# max10_schematic.net
KiCad netlist of a schematic drawn in Altium Designer
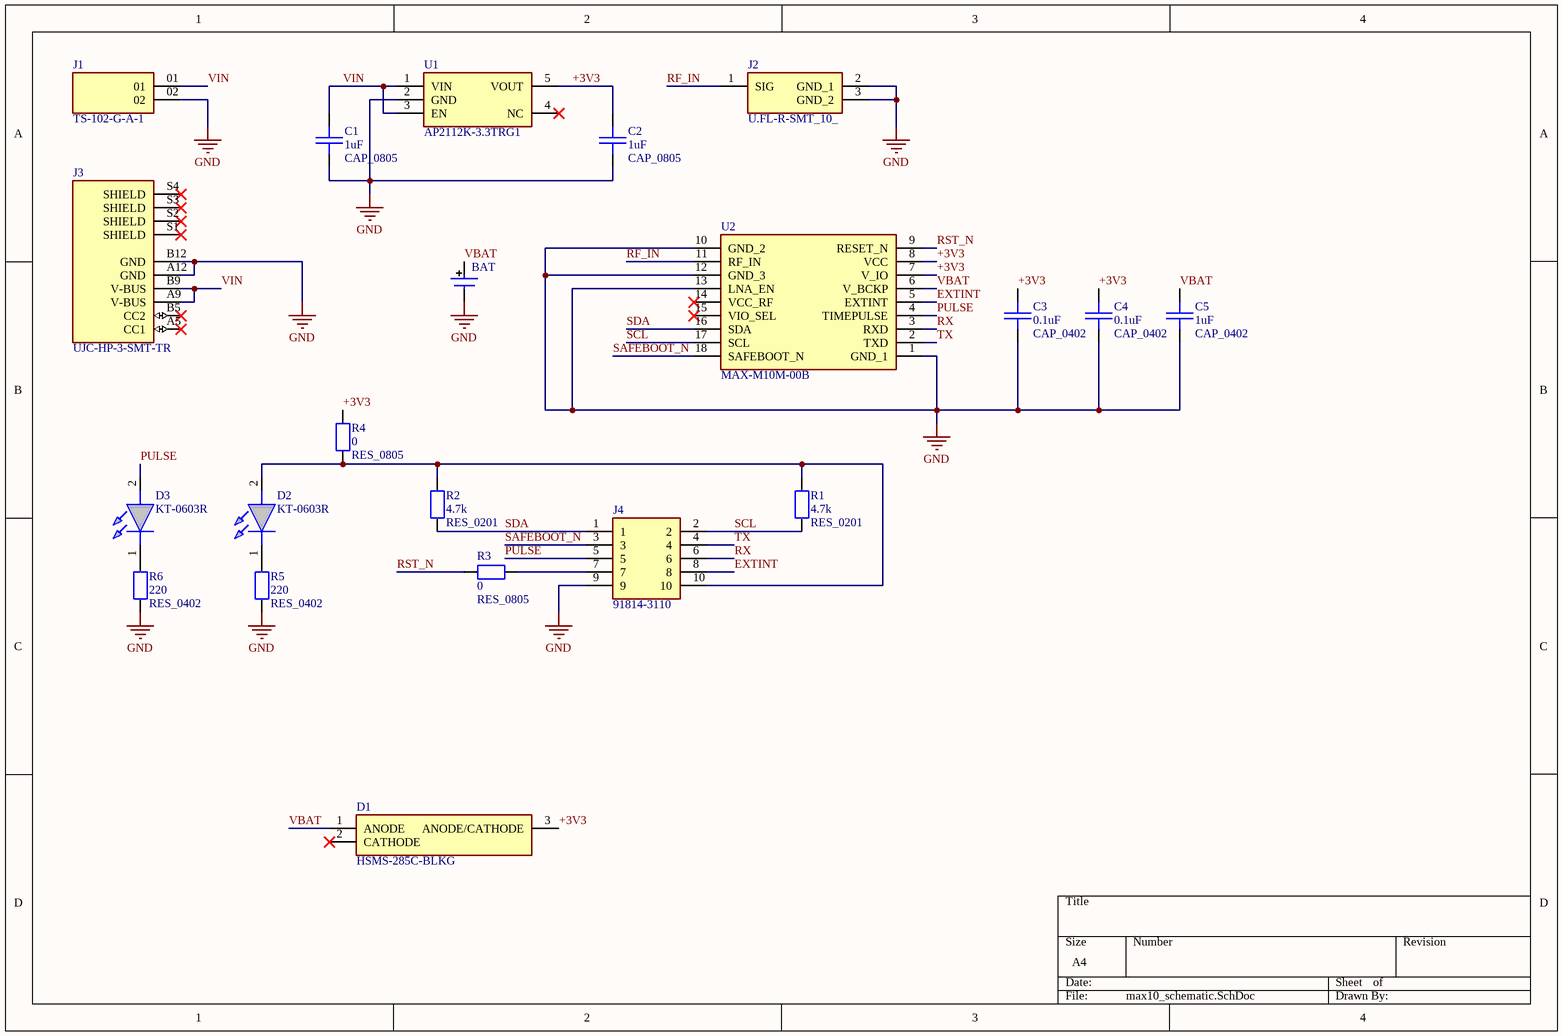
[diagram p0: max10_schematic.SchDoc]

(export (version "E")
  (design (tool "Eeschema 10.0.6"))
  (components
    (comp (ref "BAT")
      (value "MECH_BT")
      (footprint "BT_MS621FE-FL11E")
      (description "Battery")
      (libsource (lib "MECH_BT") (part "MECH_BT"))
    )
    (comp (ref "C1")
      (value "CAP_0805")
      (footprint "CAP_0805")
      (fields (field (name "ALTIUM_VALUE") "1uF"))
      (libsource (lib "smd_sch_lib") (part "CAP_0805"))
    )
    (comp (ref "C2")
      (value "CAP_0805")
      (footprint "CAP_0805")
      (fields (field (name "ALTIUM_VALUE") "1uF"))
      (libsource (lib "smd_sch_lib") (part "CAP_0805"))
    )
    (comp (ref "C3")
      (value "CAP_0402")
      (footprint "CAP_0402")
      (fields (field (name "ALTIUM_VALUE") "0.1uF"))
      (libsource (lib "smd_sch_lib") (part "CAP_0402"))
    )
    (comp (ref "C4")
      (value "CAP_0402")
      (footprint "CAP_0402")
      (fields (field (name "ALTIUM_VALUE") "0.1uF"))
      (libsource (lib "smd_sch_lib") (part "CAP_0402"))
    )
    (comp (ref "C5")
      (value "CAP_0402")
      (footprint "CAP_0402")
      (fields (field (name "ALTIUM_VALUE") "1uF"))
      (libsource (lib "smd_sch_lib") (part "CAP_0402"))
    )
    (comp (ref "D1")
      (value "HSMS-285C-BLKG")
      (footprint "SOT65P210X100-3N")
      (description "BROADCOM LIMITED - HSMS-285C-BLKG - DIODE, SCHOTTKY, SOT-323")
      (fields (field (name "MOUSER PART NUMBER") "630-HSMS-285C-BLKG"))
      (libsource (lib "HSMS-285C-BLKG") (part "HSMS-285C-BLKG"))
    )
    (comp (ref "D2")
      (value "KT-0603R")
      (footprint "LEDC1608X70N")
      (description "Red 615~630nm 1.9~2.2V 0603 Light Emitting Diodes (LED) RoHS")
      (libsource (lib "LED_KT-0603R") (part "KT-0603R"))
    )
    (comp (ref "D3")
      (value "KT-0603R")
      (footprint "LEDC1608X70N")
      (description "Red 615~630nm 1.9~2.2V 0603 Light Emitting Diodes (LED) RoHS")
      (libsource (lib "LED_KT-0603R") (part "KT-0603R"))
    )
    (comp (ref "J1")
      (value "TS-102-G-A-1")
      (footprint "SAMTEC_TS-102-G-A-1")
      (fields (field (name "MF") "{'manufacturer': u'Samtec Inc.'}"))
      (libsource (lib "TS-102-G-A-1") (part "TS-102-G-A-1"))
    )
    (comp (ref "J2")
      (value "U.FL-R-SMT_10_")
      (footprint "UFLRSMT10")
      (description "U.FL (UMCC) Connector Receptacle, Male Pin 50 Ohms Surface Mount Solder")
      (fields
        (field (name "MANUFACTURER_PART_NUMBER") "U.FL-R-SMT(10)")
        (field (name "MOUSER PART NUMBER") "798-U.FL-R-SMT10")
      )
      (libsource (lib "U.FL-R-SMT_10_") (part "U.FL-R-SMT_10_"))
    )
    (comp (ref "J3")
      (value "UJC-HP-3-SMT-TR")
      (footprint "CUI_UJC-HP-3-SMT-TR")
      (libsource (lib "UJC-HP-3-SMT-TR") (part "UJC-HP-3-SMT-TR"))
    )
    (comp (ref "J4")
      (value "91814-3110")
      (footprint "918143110")
      (fields (field (name "MOUSER PART NUMBER") "538-91814-3110"))
      (libsource (lib "91814-3110") (part "91814-3110"))
    )
    (comp (ref "R1")
      (value "RES_0201")
      (footprint "RES_0201")
      (fields (field (name "ALTIUM_VALUE") "4.7k"))
      (libsource (lib "smd_sch_lib") (part "RES_0201"))
    )
    (comp (ref "R2")
      (value "RES_0201")
      (footprint "RES_0201")
      (fields (field (name "ALTIUM_VALUE") "4.7k"))
      (libsource (lib "smd_sch_lib") (part "RES_0201"))
    )
    (comp (ref "R3")
      (value "RES_0805")
      (footprint "RES_0805")
      (fields (field (name "ALTIUM_VALUE") "0"))
      (libsource (lib "smd_sch_lib") (part "RES_0805"))
    )
    (comp (ref "R4")
      (value "RES_0805")
      (footprint "RES_0805")
      (fields (field (name "ALTIUM_VALUE") "0"))
      (libsource (lib "smd_sch_lib") (part "RES_0805"))
    )
    (comp (ref "R5")
      (value "RES_0402")
      (footprint "RES_0402")
      (fields (field (name "ALTIUM_VALUE") "220"))
      (libsource (lib "smd_sch_lib") (part "RES_0402"))
    )
    (comp (ref "R6")
      (value "RES_0402")
      (footprint "RES_0402")
      (fields (field (name "ALTIUM_VALUE") "220"))
      (libsource (lib "smd_sch_lib") (part "RES_0402"))
    )
    (comp (ref "U1")
      (value "AP2112K-3.3TRG1")
      (footprint "SOT95P285X140-5N")
      (fields (field (name "MOUSER PART NUMBER") "621-AP2112K-3.3TRG1"))
      (libsource (lib "AP2112K-3.3TRG1") (part "AP2112K-3.3TRG1"))
    )
    (comp (ref "U2")
      (value "MAX-M10M-00B")
      (footprint "MAXM10M00B")
      (description "GPS Modules u-blox M10 GNSS LCC module, firmware in ROM, crystal oscillator")
      (fields (field (name "MOUSER PART NUMBER") "377-MAX-M10M-00B"))
      (libsource (lib "MAX-M10M-00B") (part "MAX-M10M-00B"))
    )
  )
  (nets
    (net (code "1") (name "/+3V3") (class "Default")
      (node (ref "C2") (pin "2") (pintype "passive"))
      (node (ref "C3") (pin "2") (pintype "passive"))
      (node (ref "C4") (pin "2") (pintype "passive"))
      (node (ref "D1") (pin "3") (pinfunction "ANODE/CATHODE_3") (pintype "passive"))
      (node (ref "R4") (pin "2") (pintype "passive"))
      (node (ref "U1") (pin "5") (pinfunction "VOUT_5") (pintype "passive"))
      (node (ref "U2") (pin "7") (pinfunction "V_IO_7") (pintype "passive"))
      (node (ref "U2") (pin "8") (pinfunction "VCC_8") (pintype "passive"))
    )
    (net (code "2") (name "/EXTINT") (class "Default")
      (node (ref "J4") (pin "8") (pinfunction "8_8") (pintype "passive"))
      (node (ref "U2") (pin "5") (pinfunction "EXTINT_5") (pintype "passive"))
    )
    (net (code "3") (name "/PULSE") (class "Default")
      (node (ref "D3") (pin "2") (pinfunction "A_2") (pintype "passive"))
      (node (ref "J4") (pin "5") (pinfunction "5_5") (pintype "passive"))
      (node (ref "U2") (pin "4") (pinfunction "TIMEPULSE_4") (pintype "passive"))
    )
    (net (code "4") (name "/RF_IN") (class "Default")
      (node (ref "J2") (pin "1") (pinfunction "SIG_1") (pintype "passive"))
      (node (ref "U2") (pin "11") (pinfunction "RF_IN_11") (pintype "passive"))
    )
    (net (code "5") (name "/RST_N") (class "Default")
      (node (ref "R3") (pin "1") (pintype "passive"))
      (node (ref "U2") (pin "9") (pinfunction "RESET_N_9") (pintype "passive"))
    )
    (net (code "6") (name "/RX") (class "Default")
      (node (ref "J4") (pin "6") (pinfunction "6_6") (pintype "passive"))
      (node (ref "U2") (pin "3") (pinfunction "RXD_3") (pintype "passive"))
    )
    (net (code "7") (name "/SAFEBOOT_N") (class "Default")
      (node (ref "J4") (pin "3") (pinfunction "3_3") (pintype "passive"))
      (node (ref "U2") (pin "18") (pinfunction "SAFEBOOT_N_18") (pintype "passive"))
    )
    (net (code "8") (name "/SCL") (class "Default")
      (node (ref "J4") (pin "2") (pinfunction "2_2") (pintype "passive"))
      (node (ref "R1") (pin "1") (pintype "passive"))
      (node (ref "U2") (pin "17") (pinfunction "SCL_17") (pintype "passive"))
    )
    (net (code "9") (name "/SDA") (class "Default")
      (node (ref "J4") (pin "1") (pinfunction "1_1") (pintype "passive"))
      (node (ref "R2") (pin "1") (pintype "passive"))
      (node (ref "U2") (pin "16") (pinfunction "SDA_16") (pintype "passive"))
    )
    (net (code "10") (name "/TX") (class "Default")
      (node (ref "J4") (pin "4") (pinfunction "4_4") (pintype "passive"))
      (node (ref "U2") (pin "2") (pinfunction "TXD_2") (pintype "passive"))
    )
    (net (code "11") (name "/VBAT") (class "Default")
      (node (ref "BAT") (pin "1") (pinfunction "1_1") (pintype "passive"))
      (node (ref "C5") (pin "2") (pintype "passive"))
      (node (ref "D1") (pin "1") (pinfunction "ANODE_1") (pintype "passive"))
      (node (ref "U2") (pin "6") (pinfunction "V_BCKP_6") (pintype "passive"))
    )
    (net (code "12") (name "/VIN") (class "Default")
      (node (ref "C1") (pin "2") (pintype "passive"))
      (node (ref "J1") (pin "01") (pinfunction "01_01") (pintype "passive"))
      (node (ref "J3") (pin "A9") (pinfunction "V-BUS_A9") (pintype "power_in"))
      (node (ref "J3") (pin "B9") (pinfunction "V-BUS_B9") (pintype "power_in"))
      (node (ref "U1") (pin "1") (pinfunction "VIN_1") (pintype "passive"))
      (node (ref "U1") (pin "3") (pinfunction "EN_3") (pintype "passive"))
    )
    (net (code "13") (name "GND") (class "Default")
      (node (ref "BAT") (pin "2") (pinfunction "2_2") (pintype "passive"))
      (node (ref "C1") (pin "1") (pintype "passive"))
      (node (ref "C2") (pin "1") (pintype "passive"))
      (node (ref "C3") (pin "1") (pintype "passive"))
      (node (ref "C4") (pin "1") (pintype "passive"))
      (node (ref "C5") (pin "1") (pintype "passive"))
      (node (ref "J1") (pin "02") (pinfunction "02_02") (pintype "passive"))
      (node (ref "J2") (pin "2") (pinfunction "GND_1_2") (pintype "passive"))
      (node (ref "J2") (pin "3") (pinfunction "GND_2_3") (pintype "passive"))
      (node (ref "J3") (pin "A12") (pinfunction "GND_A12") (pintype "power_in"))
      (node (ref "J3") (pin "B12") (pinfunction "GND_B12") (pintype "power_in"))
      (node (ref "J4") (pin "9") (pinfunction "9_9") (pintype "passive"))
      (node (ref "R5") (pin "1") (pintype "passive"))
      (node (ref "R6") (pin "1") (pintype "passive"))
      (node (ref "U1") (pin "2") (pinfunction "GND_2") (pintype "passive"))
      (node (ref "U2") (pin "1") (pinfunction "GND_1_1") (pintype "passive"))
      (node (ref "U2") (pin "10") (pinfunction "GND_2_10") (pintype "passive"))
      (node (ref "U2") (pin "12") (pinfunction "GND_3_12") (pintype "passive"))
      (node (ref "U2") (pin "13") (pinfunction "LNA_EN_13") (pintype "passive"))
    )
    (net (code "14") (name "Net-(D2-A)") (class "Default")
      (node (ref "D2") (pin "2") (pinfunction "A_2") (pintype "passive"))
      (node (ref "J4") (pin "10") (pinfunction "10_10") (pintype "passive"))
      (node (ref "R1") (pin "2") (pintype "passive"))
      (node (ref "R2") (pin "2") (pintype "passive"))
      (node (ref "R4") (pin "1") (pintype "passive"))
    )
    (net (code "15") (name "Net-(D2-K)") (class "Default")
      (node (ref "D2") (pin "1") (pinfunction "K_1") (pintype "passive"))
      (node (ref "R5") (pin "2") (pintype "passive"))
    )
    (net (code "16") (name "Net-(D3-K)") (class "Default")
      (node (ref "D3") (pin "1") (pinfunction "K_1") (pintype "passive"))
      (node (ref "R6") (pin "2") (pintype "passive"))
    )
    (net (code "17") (name "Net-(J4-Pad7)") (class "Default")
      (node (ref "J4") (pin "7") (pinfunction "7_7") (pintype "passive"))
      (node (ref "R3") (pin "2") (pintype "passive"))
    )
    (net (code "18") (name "unconnected-(D1-CATHODE-Pad2)") (class "Default")
      (node (ref "D1") (pin "2") (pinfunction "CATHODE_2") (pintype "passive+no_connect"))
    )
    (net (code "19") (name "unconnected-(J3-CC1-PadA5)") (class "Default")
      (node (ref "J3") (pin "A5") (pinfunction "CC1_A5") (pintype "bidirectional+no_connect"))
    )
    (net (code "20") (name "unconnected-(J3-CC2-PadB5)") (class "Default")
      (node (ref "J3") (pin "B5") (pinfunction "CC2_B5") (pintype "bidirectional+no_connect"))
    )
    (net (code "21") (name "unconnected-(J3-SHIELD-PadS1)") (class "Default")
      (node (ref "J3") (pin "S1") (pinfunction "SHIELD_S1") (pintype "passive+no_connect"))
    )
    (net (code "22") (name "unconnected-(J3-SHIELD-PadS2)") (class "Default")
      (node (ref "J3") (pin "S2") (pinfunction "SHIELD_S2") (pintype "passive+no_connect"))
    )
    (net (code "23") (name "unconnected-(J3-SHIELD-PadS3)") (class "Default")
      (node (ref "J3") (pin "S3") (pinfunction "SHIELD_S3") (pintype "passive+no_connect"))
    )
    (net (code "24") (name "unconnected-(J3-SHIELD-PadS4)") (class "Default")
      (node (ref "J3") (pin "S4") (pinfunction "SHIELD_S4") (pintype "passive+no_connect"))
    )
    (net (code "25") (name "unconnected-(U1-NC-Pad4)") (class "Default")
      (node (ref "U1") (pin "4") (pinfunction "NC_4") (pintype "passive+no_connect"))
    )
    (net (code "26") (name "unconnected-(U2-VCC_RF-Pad14)") (class "Default")
      (node (ref "U2") (pin "14") (pinfunction "VCC_RF_14") (pintype "passive+no_connect"))
    )
    (net (code "27") (name "unconnected-(U2-VIO_SEL-Pad15)") (class "Default")
      (node (ref "U2") (pin "15") (pinfunction "VIO_SEL_15") (pintype "passive+no_connect"))
    )
  )
)
